# MotorBoardDev.net
KiCad netlist of a schematic drawn in EAGLE
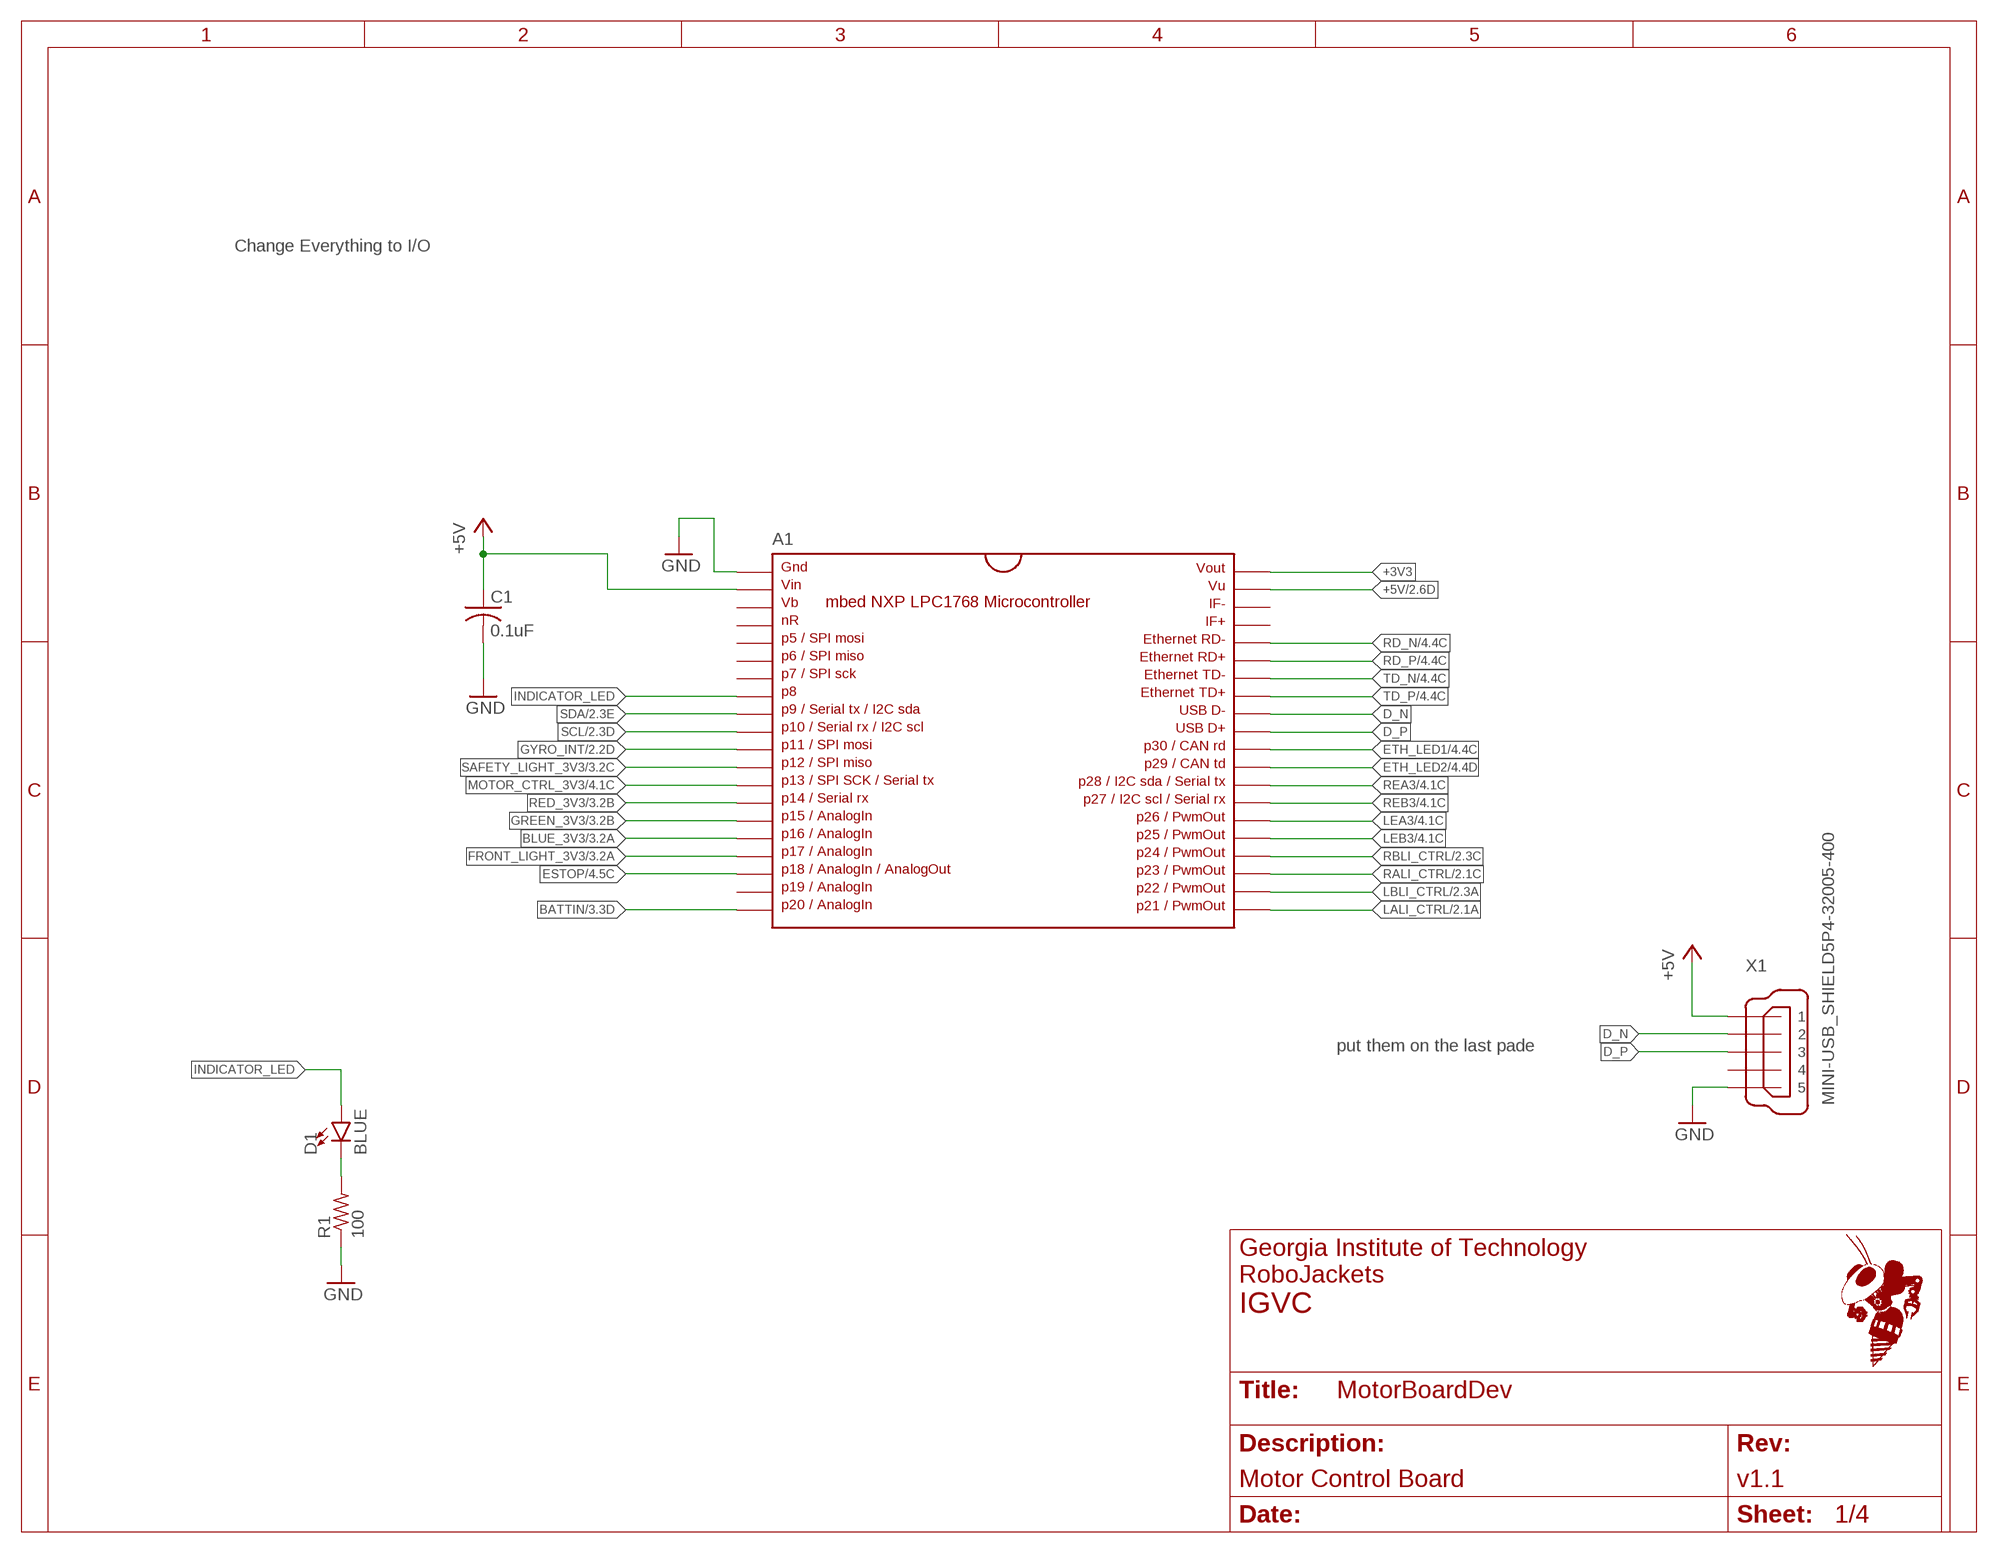
[diagram p0: schematic, sheet 1]
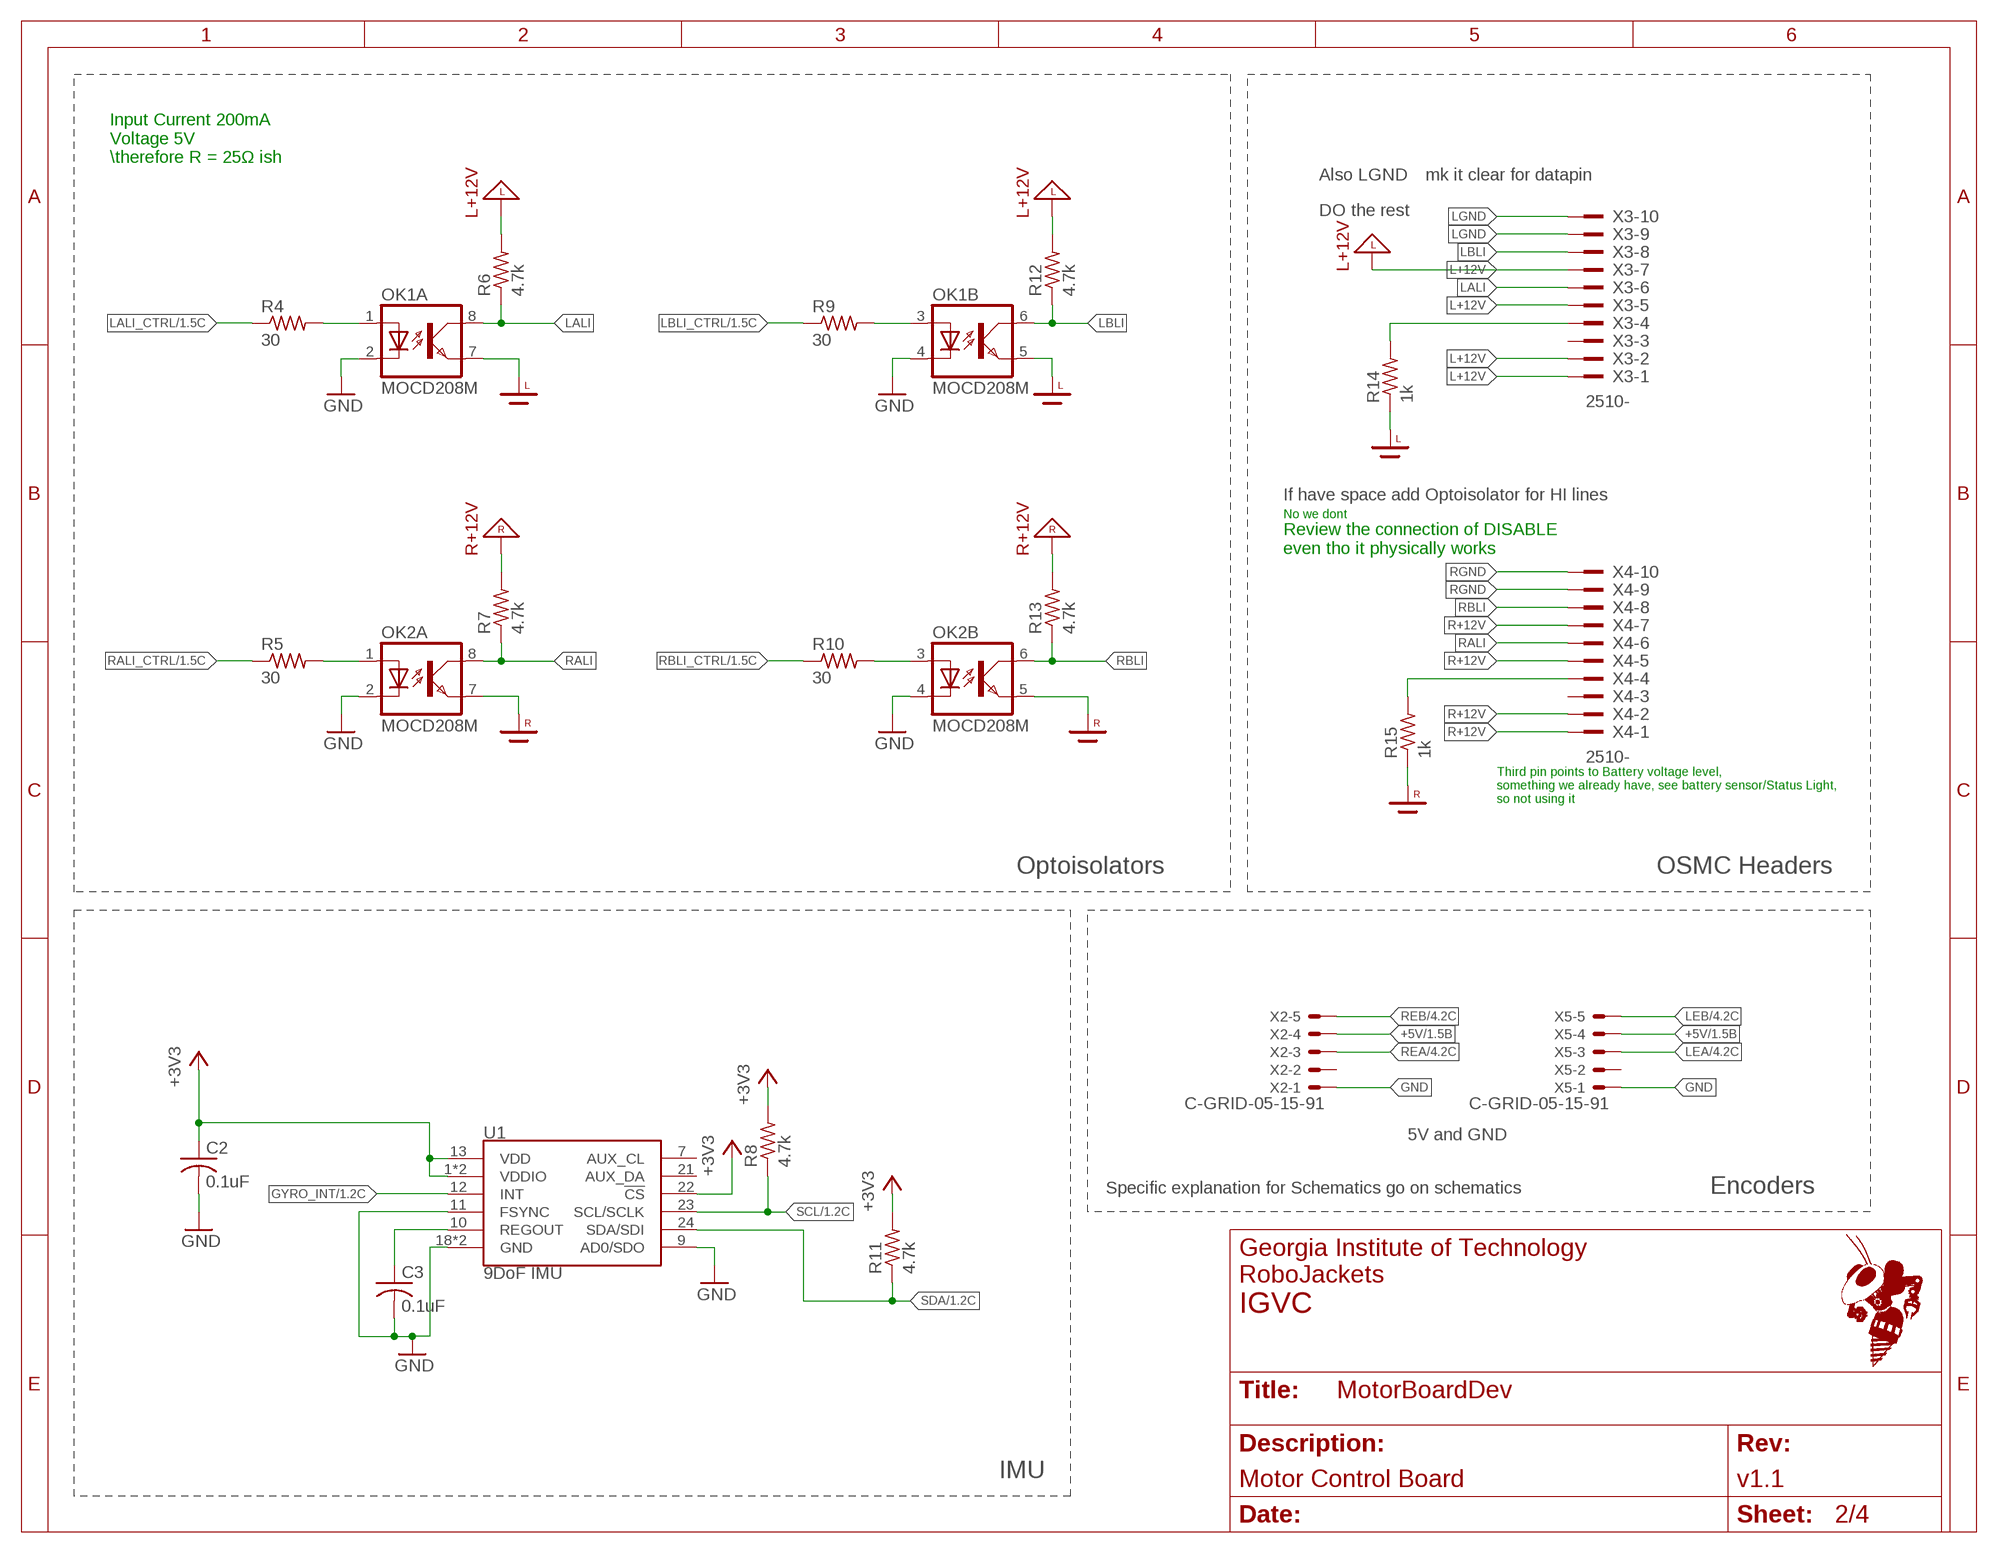
[diagram p1: schematic, sheet 2]
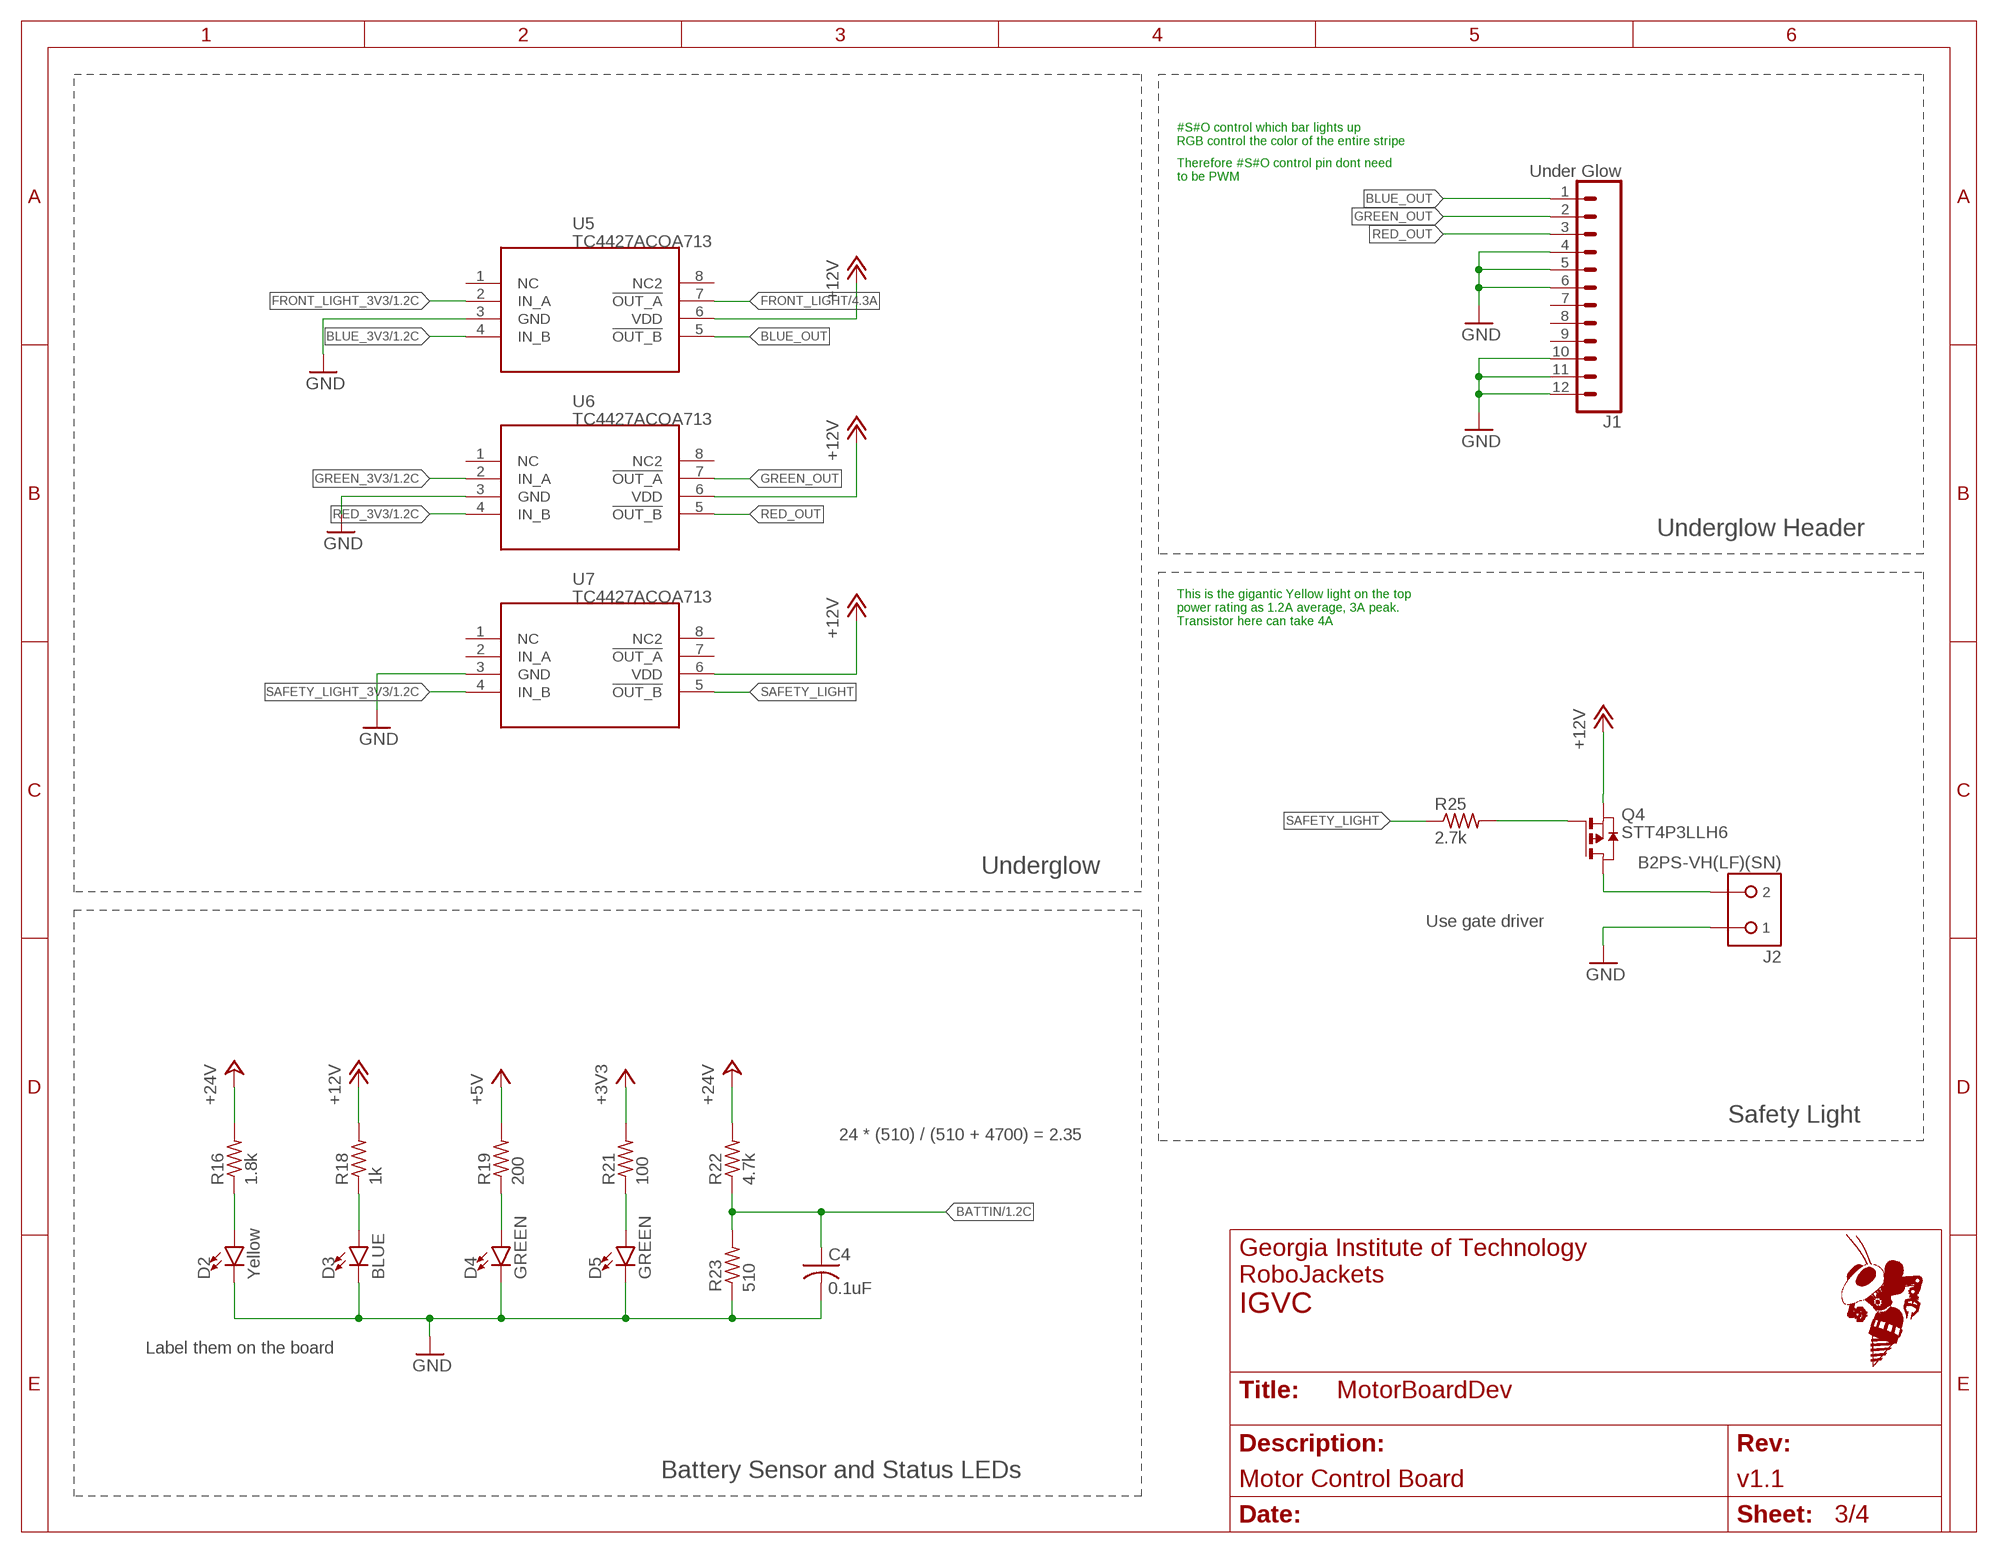
[diagram p2: schematic, sheet 3]
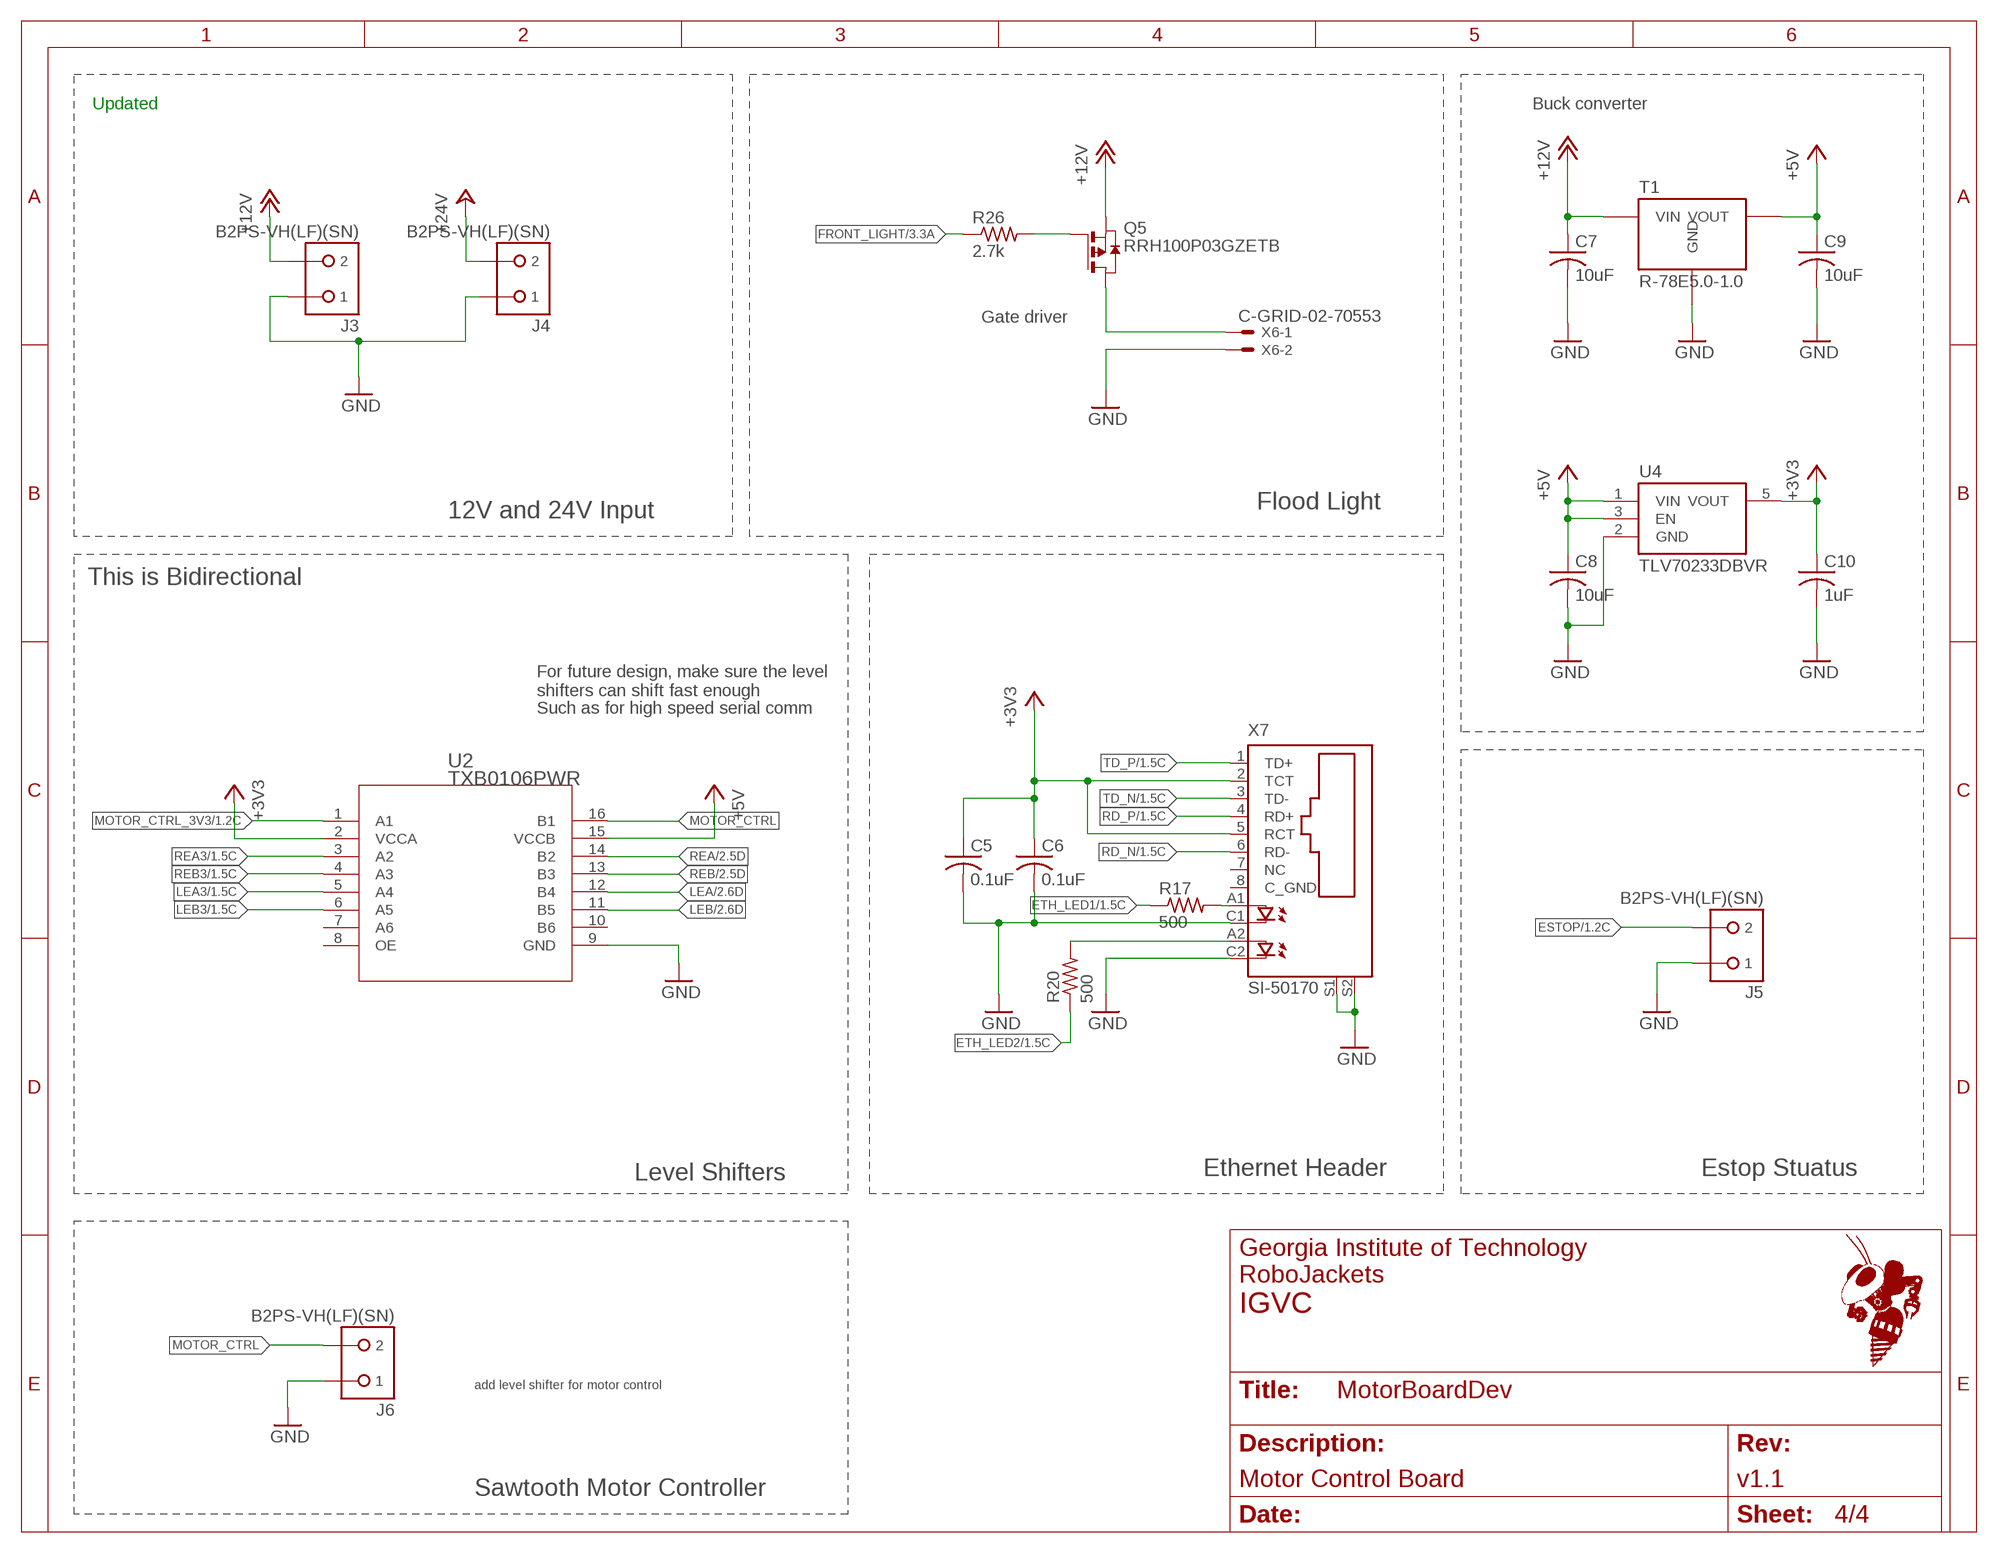
[diagram p3: schematic, sheet 4]

(export (version "E")
  (design (tool "Eeschema 10.0.6"))
  (components
    (comp (ref "A1")
      (value "MBED1768")
      (footprint "eagle-import:SPARKFUN-BOARDS_DIL40_0.9")
      (libsource (lib "eagle-import") (part "SPARKFUN-BOARDS_MBED_NXP_LPC1768"))
    )
    (comp (ref "C1")
      (value "0.1uF")
      (footprint "eagle-import:C0603")
      (libsource (lib "eagle-import") (part "C-USC0603"))
    )
    (comp (ref "D1")
      (value "BLUE")
      (footprint "eagle-import:LED-0603")
      (libsource (lib "eagle-import") (part "LED-BLUE0603"))
    )
    (comp (ref "R1")
      (value "100")
      (footprint "eagle-import:R0603")
      (libsource (lib "eagle-import") (part "R-US_R0603"))
    )
    (comp (ref "X1")
      (value "MINI-USB_SHIELD5P4-32005-400")
      (footprint "eagle-import:32005-400")
      (libsource (lib "eagle-import") (part "MINI-USB_SHIELD5P4-32005-400"))
    )
    (comp (ref "C4")
      (value "0.1uF")
      (footprint "eagle-import:C0603")
      (libsource (lib "eagle-import") (part "C-USC0603"))
    )
    (comp (ref "D2")
      (value "Yellow")
      (footprint "eagle-import:LED-0603")
      (libsource (lib "eagle-import") (part "LED-YELLOW0603"))
    )
    (comp (ref "D3")
      (value "BLUE")
      (footprint "eagle-import:LED-0603")
      (libsource (lib "eagle-import") (part "LED-BLUE0603"))
    )
    (comp (ref "D4")
      (value "GREEN")
      (footprint "eagle-import:LED-0603")
      (libsource (lib "eagle-import") (part "LED-GREEN0603"))
    )
    (comp (ref "D5")
      (value "GREEN")
      (footprint "eagle-import:LED-0603")
      (libsource (lib "eagle-import") (part "LED-GREEN0603"))
    )
    (comp (ref "J1")
      (value "Under Glow")
      (footprint "eagle-import:1X12_LOCK_LONGPADS")
      (libsource (lib "eagle-import") (part "CONN_12LOCK_LONGPADS"))
    )
    (comp (ref "J2")
      (value "B2PS-VH(LF)(SN)")
      (footprint "eagle-import:B2PS-CENTERED")
      (libsource (lib "eagle-import") (part "B2P?-VH(LF)(SN)S"))
    )
    (comp (ref "Q4")
      (value "STT4P3LLH6")
      (footprint "eagle-import:SOT23-6")
      (libsource (lib "eagle-import") (part "STT4P3LLH6"))
    )
    (comp (ref "R16")
      (value "1.8k")
      (footprint "eagle-import:R0603")
      (libsource (lib "eagle-import") (part "R-US_R0603"))
    )
    (comp (ref "R18")
      (value "1k")
      (footprint "eagle-import:R0603")
      (libsource (lib "eagle-import") (part "R-US_R0603"))
    )
    (comp (ref "R19")
      (value "200")
      (footprint "eagle-import:R0603")
      (libsource (lib "eagle-import") (part "R-US_R0603"))
    )
    (comp (ref "R21")
      (value "100")
      (footprint "eagle-import:R0603")
      (libsource (lib "eagle-import") (part "R-US_R0603"))
    )
    (comp (ref "R22")
      (value "4.7k")
      (footprint "eagle-import:R0603")
      (libsource (lib "eagle-import") (part "R-US_R0603"))
    )
    (comp (ref "R23")
      (value "510")
      (footprint "eagle-import:R0603")
      (libsource (lib "eagle-import") (part "R-US_R0603"))
    )
    (comp (ref "R25")
      (value "2.7k")
      (footprint "eagle-import:R0603")
      (libsource (lib "eagle-import") (part "R-US_R0603"))
    )
    (comp (ref "U5")
      (value "TC4427ACOA713")
      (footprint "eagle-import:SOIC-8")
      (libsource (lib "eagle-import") (part "TC4427ACOA713"))
    )
    (comp (ref "U6")
      (value "TC4427ACOA713")
      (footprint "eagle-import:SOIC-8")
      (libsource (lib "eagle-import") (part "TC4427ACOA713"))
    )
    (comp (ref "U7")
      (value "TC4427ACOA713")
      (footprint "eagle-import:SOIC-8")
      (libsource (lib "eagle-import") (part "TC4427ACOA713"))
    )
    (comp (ref "C5")
      (value "0.1uF")
      (footprint "eagle-import:C0603")
      (libsource (lib "eagle-import") (part "C-USC0603"))
    )
    (comp (ref "C6")
      (value "0.1uF")
      (footprint "eagle-import:C0603")
      (libsource (lib "eagle-import") (part "C-USC0603"))
    )
    (comp (ref "C7")
      (value "10uF")
      (footprint "eagle-import:C0805")
      (libsource (lib "eagle-import") (part "C-USC0805"))
    )
    (comp (ref "C8")
      (value "10uF")
      (footprint "eagle-import:C0805")
      (libsource (lib "eagle-import") (part "C-USC0805"))
    )
    (comp (ref "C9")
      (value "10uF")
      (footprint "eagle-import:C0805")
      (libsource (lib "eagle-import") (part "C-USC0805"))
    )
    (comp (ref "C10")
      (value "1uF")
      (footprint "eagle-import:C0805")
      (libsource (lib "eagle-import") (part "C-USC0805"))
    )
    (comp (ref "J3")
      (value "B2PS-VH(LF)(SN)")
      (footprint "eagle-import:B2PS-CENTERED")
      (libsource (lib "eagle-import") (part "B2P?-VH(LF)(SN)S"))
    )
    (comp (ref "J4")
      (value "B2PS-VH(LF)(SN)")
      (footprint "eagle-import:B2PS-CENTERED")
      (libsource (lib "eagle-import") (part "B2P?-VH(LF)(SN)S"))
    )
    (comp (ref "J5")
      (value "B2PS-VH(LF)(SN)")
      (footprint "eagle-import:B2PS-CENTERED")
      (libsource (lib "eagle-import") (part "B2P?-VH(LF)(SN)S"))
    )
    (comp (ref "J6")
      (value "B2PS-VH(LF)(SN)")
      (footprint "eagle-import:B2PS-CENTERED")
      (libsource (lib "eagle-import") (part "B2P?-VH(LF)(SN)S"))
    )
    (comp (ref "Q5")
      (value "RRH100P03GZETB")
      (footprint "eagle-import:SOIC-8")
      (libsource (lib "eagle-import") (part "RRH100P03GZETB"))
    )
    (comp (ref "R17")
      (value "500")
      (footprint "eagle-import:R0603")
      (libsource (lib "eagle-import") (part "R-US_R0603"))
    )
    (comp (ref "R20")
      (value "500")
      (footprint "eagle-import:R0603")
      (libsource (lib "eagle-import") (part "R-US_R0603"))
    )
    (comp (ref "R26")
      (value "2.7k")
      (footprint "eagle-import:R0603")
      (libsource (lib "eagle-import") (part "R-US_R0603"))
    )
    (comp (ref "T1")
      (value "R-78E5.0-1.0")
      (footprint "eagle-import:R-78E")
      (libsource (lib "eagle-import") (part "R-78E5.0-1.0"))
    )
    (comp (ref "U2")
      (value "TXB0106PWR")
      (footprint "eagle-import:PW16")
      (libsource (lib "eagle-import") (part "TXB0106PWR"))
    )
    (comp (ref "U4")
      (value "TLV70233DBVR")
      (footprint "eagle-import:SOT-23-5")
      (libsource (lib "eagle-import") (part "TLV70233DBVR"))
    )
    (comp (ref "X6")
      (value "C-GRID-02-70553")
      (footprint "eagle-import:70553-02")
      (libsource (lib "eagle-import") (part "C-GRID-02-70553"))
    )
    (comp (ref "X7")
      (value "SI-50170")
      (footprint "eagle-import:SI-50170")
      (libsource (lib "eagle-import") (part "SI-50170"))
    )
    (comp (ref "C2")
      (value "0.1uF")
      (footprint "eagle-import:C0603")
      (libsource (lib "eagle-import") (part "C-USC0603"))
    )
    (comp (ref "C3")
      (value "0.1uF")
      (footprint "eagle-import:C0603")
      (libsource (lib "eagle-import") (part "C-USC0603"))
    )
    (comp (ref "OK1")
      (value "MOCD208M")
      (footprint "eagle-import:SOIC08-FAIRCHILD")
      (fields (field (name "MF") "FAIRCHILD SEMICONDUCTOR"))
      (libsource (lib "eagle-import") (part "MOCD20M8"))
    )
    (comp (ref "OK2")
      (value "MOCD208M")
      (footprint "eagle-import:SOIC08-FAIRCHILD")
      (fields (field (name "MF") "FAIRCHILD SEMICONDUCTOR"))
      (libsource (lib "eagle-import") (part "MOCD20M8"))
    )
    (comp (ref "R4")
      (value "30")
      (footprint "eagle-import:R0603")
      (libsource (lib "eagle-import") (part "R-US_R0603"))
    )
    (comp (ref "R5")
      (value "30")
      (footprint "eagle-import:R0603")
      (libsource (lib "eagle-import") (part "R-US_R0603"))
    )
    (comp (ref "R6")
      (value "4.7k")
      (footprint "eagle-import:R0603")
      (libsource (lib "eagle-import") (part "R-US_R0603"))
    )
    (comp (ref "R7")
      (value "4.7k")
      (footprint "eagle-import:R0603")
      (libsource (lib "eagle-import") (part "R-US_R0603"))
    )
    (comp (ref "R8")
      (value "4.7k")
      (footprint "eagle-import:R0603")
      (libsource (lib "eagle-import") (part "R-US_R0603"))
    )
    (comp (ref "R9")
      (value "30")
      (footprint "eagle-import:R0603")
      (libsource (lib "eagle-import") (part "R-US_R0603"))
    )
    (comp (ref "R10")
      (value "30")
      (footprint "eagle-import:R0603")
      (libsource (lib "eagle-import") (part "R-US_R0603"))
    )
    (comp (ref "R11")
      (value "4.7k")
      (footprint "eagle-import:R0603")
      (libsource (lib "eagle-import") (part "R-US_R0603"))
    )
    (comp (ref "R12")
      (value "4.7k")
      (footprint "eagle-import:R0603")
      (libsource (lib "eagle-import") (part "R-US_R0603"))
    )
    (comp (ref "R13")
      (value "4.7k")
      (footprint "eagle-import:R0603")
      (libsource (lib "eagle-import") (part "R-US_R0603"))
    )
    (comp (ref "R14")
      (value "1k")
      (footprint "eagle-import:R0603")
      (libsource (lib "eagle-import") (part "R-US_R0603"))
    )
    (comp (ref "R15")
      (value "1k")
      (footprint "eagle-import:R0603")
      (libsource (lib "eagle-import") (part "R-US_R0603"))
    )
    (comp (ref "U1")
      (value "9DoF IMU")
      (footprint "eagle-import:QFN24-3X3")
      (libsource (lib "eagle-import") (part "MPU-9250"))
    )
    (comp (ref "X2")
      (value "C-GRID-05-15-91")
      (footprint "eagle-import:15-91-05")
      (libsource (lib "eagle-import") (part "C-GRID-05-15-91"))
    )
    (comp (ref "X3")
      (value "2510-")
      (footprint "eagle-import:PAK100_2500-10")
      (fields (field (name "MF") "3M") (field (name "MPN") "2510-6002UB"))
      (libsource (lib "eagle-import") (part "2510-"))
    )
    (comp (ref "X4")
      (value "2510-")
      (footprint "eagle-import:PAK100_2500-10")
      (fields (field (name "MF") "3M") (field (name "MPN") "2510-6002UB"))
      (libsource (lib "eagle-import") (part "2510-"))
    )
    (comp (ref "X5")
      (value "C-GRID-05-15-91")
      (footprint "eagle-import:15-91-05")
      (libsource (lib "eagle-import") (part "C-GRID-05-15-91"))
    )
  )
  (nets
    (net (code "1") (name "+3V3") (class "Default")
      (node (ref "A1") (pin "40") (pinfunction "P$40_40") (pintype "bidirectional"))
      (node (ref "C10") (pin "1") (pinfunction "1_1") (pintype "passive"))
      (node (ref "C2") (pin "1") (pinfunction "1_1") (pintype "passive"))
      (node (ref "C5") (pin "1") (pinfunction "1_1") (pintype "passive"))
      (node (ref "C6") (pin "1") (pinfunction "1_1") (pintype "passive"))
      (node (ref "R11") (pin "2") (pinfunction "2_2") (pintype "passive"))
      (node (ref "R21") (pin "2") (pinfunction "2_2") (pintype "passive"))
      (node (ref "R8") (pin "2") (pinfunction "2_2") (pintype "passive"))
      (node (ref "U1") (pin "1") (pinfunction "VDDIO_1") (pintype "bidirectional"))
      (node (ref "U1") (pin "13") (pinfunction "VDD_13") (pintype "bidirectional"))
      (node (ref "U1") (pin "22") (pinfunction "~{CS}_22") (pintype "bidirectional"))
      (node (ref "U1") (pin "8") (pinfunction "VDDIO_8") (pintype "bidirectional"))
      (node (ref "U2") (pin "2") (pinfunction "VCCA_2") (pintype "power_in"))
      (node (ref "U4") (pin "5") (pinfunction "VOUT_5") (pintype "bidirectional"))
      (node (ref "X7") (pin "2") (pinfunction "TCT_2") (pintype "passive"))
      (node (ref "X7") (pin "5") (pinfunction "RCT_5") (pintype "passive"))
    )
    (net (code "2") (name "+5V") (class "Default")
      (node (ref "A1") (pin "2") (pinfunction "P$2_2") (pintype "bidirectional"))
      (node (ref "A1") (pin "39") (pinfunction "P$39_39") (pintype "bidirectional"))
      (node (ref "C1") (pin "1") (pinfunction "1_1") (pintype "passive"))
      (node (ref "C8") (pin "1") (pinfunction "1_1") (pintype "passive"))
      (node (ref "C9") (pin "1") (pinfunction "1_1") (pintype "passive"))
      (node (ref "R19") (pin "2") (pinfunction "2_2") (pintype "passive"))
      (node (ref "T1") (pin "3") (pinfunction "VOUT_3") (pintype "bidirectional"))
      (node (ref "U2") (pin "15") (pinfunction "VCCB_15") (pintype "power_in"))
      (node (ref "U4") (pin "1") (pinfunction "VIN_1") (pintype "bidirectional"))
      (node (ref "U4") (pin "3") (pinfunction "EN_3") (pintype "bidirectional"))
      (node (ref "X1") (pin "1") (pinfunction "1_1") (pintype "passive"))
      (node (ref "X2") (pin "4") (pinfunction "S_4") (pintype "passive"))
      (node (ref "X5") (pin "4") (pinfunction "S_4") (pintype "passive"))
    )
    (net (code "3") (name "+12V") (class "Default")
      (node (ref "C7") (pin "1") (pinfunction "1_1") (pintype "passive"))
      (node (ref "J3") (pin "2") (pinfunction "2_2") (pintype "bidirectional"))
      (node (ref "Q4") (pin "4") (pinfunction "S_4") (pintype "passive"))
      (node (ref "Q5") (pin "1") (pinfunction "S_1") (pintype "passive"))
      (node (ref "Q5") (pin "2") (pinfunction "S_2") (pintype "passive"))
      (node (ref "Q5") (pin "3") (pinfunction "S_3") (pintype "passive"))
      (node (ref "R18") (pin "2") (pinfunction "2_2") (pintype "passive"))
      (node (ref "T1") (pin "1") (pinfunction "VIN_1") (pintype "bidirectional"))
      (node (ref "U5") (pin "6") (pinfunction "VDD_6") (pintype "bidirectional"))
      (node (ref "U6") (pin "6") (pinfunction "VDD_6") (pintype "bidirectional"))
      (node (ref "U7") (pin "6") (pinfunction "VDD_6") (pintype "bidirectional"))
    )
    (net (code "4") (name "+24V") (class "Default")
      (node (ref "J4") (pin "2") (pinfunction "2_2") (pintype "bidirectional"))
      (node (ref "R16") (pin "2") (pinfunction "2_2") (pintype "passive"))
      (node (ref "R22") (pin "2") (pinfunction "2_2") (pintype "passive"))
    )
    (net (code "5") (name "BATTIN") (class "Default")
      (node (ref "A1") (pin "20") (pinfunction "P$20_20") (pintype "bidirectional"))
      (node (ref "C4") (pin "1") (pinfunction "1_1") (pintype "passive"))
      (node (ref "R22") (pin "1") (pinfunction "1_1") (pintype "passive"))
      (node (ref "R23") (pin "2") (pinfunction "2_2") (pintype "passive"))
    )
    (net (code "6") (name "BLUE_3V3") (class "Default")
      (node (ref "A1") (pin "16") (pinfunction "P$16_16") (pintype "bidirectional"))
      (node (ref "U5") (pin "4") (pinfunction "IN_B_4") (pintype "bidirectional"))
    )
    (net (code "7") (name "BLUE_OUT") (class "Default")
      (node (ref "J1") (pin "1") (pinfunction "1_1") (pintype "passive"))
      (node (ref "U5") (pin "5") (pinfunction "~{OUT_B}_5") (pintype "bidirectional"))
    )
    (net (code "8") (name "D_N") (class "Default")
      (node (ref "A1") (pin "32") (pinfunction "P$32_32") (pintype "bidirectional"))
      (node (ref "X1") (pin "2") (pinfunction "2_2") (pintype "passive"))
    )
    (net (code "9") (name "D_P") (class "Default")
      (node (ref "A1") (pin "31") (pinfunction "P$31_31") (pintype "bidirectional"))
      (node (ref "X1") (pin "3") (pinfunction "3_3") (pintype "passive"))
    )
    (net (code "10") (name "ESTOP") (class "Default")
      (node (ref "A1") (pin "18") (pinfunction "P$18_18") (pintype "bidirectional"))
      (node (ref "J5") (pin "2") (pinfunction "2_2") (pintype "bidirectional"))
    )
    (net (code "11") (name "ETH_LED1") (class "Default")
      (node (ref "A1") (pin "30") (pinfunction "P$30_30") (pintype "bidirectional"))
      (node (ref "R17") (pin "1") (pinfunction "1_1") (pintype "passive"))
    )
    (net (code "12") (name "ETH_LED2") (class "Default")
      (node (ref "A1") (pin "29") (pinfunction "P$29_29") (pintype "bidirectional"))
      (node (ref "R20") (pin "1") (pinfunction "1_1") (pintype "passive"))
    )
    (net (code "13") (name "FRONT_LIGHT") (class "Default")
      (node (ref "R26") (pin "1") (pinfunction "1_1") (pintype "passive"))
      (node (ref "U5") (pin "7") (pinfunction "~{OUT_A}_7") (pintype "bidirectional"))
    )
    (net (code "14") (name "FRONT_LIGHT_3V3") (class "Default")
      (node (ref "A1") (pin "17") (pinfunction "P$17_17") (pintype "bidirectional"))
      (node (ref "U5") (pin "2") (pinfunction "IN_A_2") (pintype "bidirectional"))
    )
    (net (code "15") (name "GND") (class "Default")
      (node (ref "A1") (pin "1") (pinfunction "P$1_1") (pintype "bidirectional"))
      (node (ref "C1") (pin "2") (pinfunction "2_2") (pintype "passive"))
      (node (ref "C10") (pin "2") (pinfunction "2_2") (pintype "passive"))
      (node (ref "C2") (pin "2") (pinfunction "2_2") (pintype "passive"))
      (node (ref "C3") (pin "2") (pinfunction "2_2") (pintype "passive"))
      (node (ref "C4") (pin "2") (pinfunction "2_2") (pintype "passive"))
      (node (ref "C5") (pin "2") (pinfunction "2_2") (pintype "passive"))
      (node (ref "C6") (pin "2") (pinfunction "2_2") (pintype "passive"))
      (node (ref "C7") (pin "2") (pinfunction "2_2") (pintype "passive"))
      (node (ref "C8") (pin "2") (pinfunction "2_2") (pintype "passive"))
      (node (ref "C9") (pin "2") (pinfunction "2_2") (pintype "passive"))
      (node (ref "D2") (pin "C") (pinfunction "C_C") (pintype "passive"))
      (node (ref "D3") (pin "C") (pinfunction "C_C") (pintype "passive"))
      (node (ref "D4") (pin "C") (pinfunction "C_C") (pintype "passive"))
      (node (ref "D5") (pin "C") (pinfunction "C_C") (pintype "passive"))
      (node (ref "J1") (pin "10") (pinfunction "10_10") (pintype "passive"))
      (node (ref "J1") (pin "11") (pinfunction "11_11") (pintype "passive"))
      (node (ref "J1") (pin "12") (pinfunction "12_12") (pintype "passive"))
      (node (ref "J1") (pin "4") (pinfunction "4_4") (pintype "passive"))
      (node (ref "J1") (pin "5") (pinfunction "5_5") (pintype "passive"))
      (node (ref "J1") (pin "6") (pinfunction "6_6") (pintype "passive"))
      (node (ref "J2") (pin "1") (pinfunction "1_1") (pintype "bidirectional"))
      (node (ref "J3") (pin "1") (pinfunction "1_1") (pintype "bidirectional"))
      (node (ref "J4") (pin "1") (pinfunction "1_1") (pintype "bidirectional"))
      (node (ref "J5") (pin "1") (pinfunction "1_1") (pintype "bidirectional"))
      (node (ref "J6") (pin "1") (pinfunction "1_1") (pintype "bidirectional"))
      (node (ref "OK1") (pin "2") (pinfunction "C_2") (pintype "passive"))
      (node (ref "OK1") (pin "4") (pinfunction "C_4") (pintype "passive"))
      (node (ref "OK2") (pin "2") (pinfunction "C_2") (pintype "passive"))
      (node (ref "OK2") (pin "4") (pinfunction "C_4") (pintype "passive"))
      (node (ref "R1") (pin "1") (pinfunction "1_1") (pintype "passive"))
      (node (ref "R23") (pin "1") (pinfunction "1_1") (pintype "passive"))
      (node (ref "T1") (pin "2") (pinfunction "GND_2") (pintype "bidirectional"))
      (node (ref "U1") (pin "11") (pinfunction "FSYNC_11") (pintype "bidirectional"))
      (node (ref "U1") (pin "18") (pinfunction "GND_18") (pintype "bidirectional"))
      (node (ref "U1") (pin "20") (pinfunction "GND_20") (pintype "bidirectional"))
      (node (ref "U1") (pin "9") (pinfunction "AD0/SDO_9") (pintype "bidirectional"))
      (node (ref "U2") (pin "9") (pinfunction "GND_9") (pintype "power_in"))
      (node (ref "U4") (pin "2") (pinfunction "GND_2") (pintype "bidirectional"))
      (node (ref "U5") (pin "3") (pinfunction "GND_3") (pintype "bidirectional"))
      (node (ref "U6") (pin "3") (pinfunction "GND_3") (pintype "bidirectional"))
      (node (ref "U7") (pin "3") (pinfunction "GND_3") (pintype "bidirectional"))
      (node (ref "X1") (pin "5") (pinfunction "5_5") (pintype "passive"))
      (node (ref "X2") (pin "1") (pinfunction "S_1") (pintype "passive"))
      (node (ref "X5") (pin "1") (pinfunction "S_1") (pintype "passive"))
      (node (ref "X6") (pin "2") (pinfunction "S_2") (pintype "passive"))
      (node (ref "X7") (pin "C1") (pinfunction "C_C1") (pintype "passive"))
      (node (ref "X7") (pin "C2") (pinfunction "C1_C2") (pintype "passive"))
      (node (ref "X7") (pin "S1") (pinfunction "S1_S1") (pintype "passive"))
      (node (ref "X7") (pin "S2") (pinfunction "S2_S2") (pintype "passive"))
    )
    (net (code "16") (name "GREEN_3V3") (class "Default")
      (node (ref "A1") (pin "15") (pinfunction "P$15_15") (pintype "bidirectional"))
      (node (ref "U6") (pin "2") (pinfunction "IN_A_2") (pintype "bidirectional"))
    )
    (net (code "17") (name "GREEN_OUT") (class "Default")
      (node (ref "J1") (pin "2") (pinfunction "2_2") (pintype "passive"))
      (node (ref "U6") (pin "7") (pinfunction "~{OUT_A}_7") (pintype "bidirectional"))
    )
    (net (code "18") (name "GYRO_INT") (class "Default")
      (node (ref "A1") (pin "11") (pinfunction "P$11_11") (pintype "bidirectional"))
      (node (ref "U1") (pin "12") (pinfunction "INT_12") (pintype "bidirectional"))
    )
    (net (code "19") (name "INDICATOR_LED") (class "Default")
      (node (ref "A1") (pin "8") (pinfunction "P$8_8") (pintype "bidirectional"))
      (node (ref "D1") (pin "A") (pinfunction "A_A") (pintype "passive"))
    )
    (net (code "20") (name "L+12V") (class "Default")
      (node (ref "R12") (pin "2") (pinfunction "2_2") (pintype "passive"))
      (node (ref "R6") (pin "2") (pinfunction "2_2") (pintype "passive"))
      (node (ref "X3") (pin "1") (pinfunction "KL_1") (pintype "passive"))
      (node (ref "X3") (pin "2") (pinfunction "KL_2") (pintype "passive"))
      (node (ref "X3") (pin "5") (pinfunction "KL_5") (pintype "passive"))
      (node (ref "X3") (pin "7") (pinfunction "KL_7") (pintype "passive"))
    )
    (net (code "21") (name "LALI") (class "Default")
      (node (ref "OK1") (pin "8") (pinfunction "COL_8") (pintype "passive"))
      (node (ref "R6") (pin "1") (pinfunction "1_1") (pintype "passive"))
      (node (ref "X3") (pin "6") (pinfunction "KL_6") (pintype "passive"))
    )
    (net (code "22") (name "LALI_CTRL") (class "Default")
      (node (ref "A1") (pin "21") (pinfunction "P$21_21") (pintype "bidirectional"))
      (node (ref "R4") (pin "1") (pinfunction "1_1") (pintype "passive"))
    )
    (net (code "23") (name "LBLI") (class "Default")
      (node (ref "OK1") (pin "6") (pinfunction "COL_6") (pintype "passive"))
      (node (ref "R12") (pin "1") (pinfunction "1_1") (pintype "passive"))
      (node (ref "X3") (pin "8") (pinfunction "KL_8") (pintype "passive"))
    )
    (net (code "24") (name "LBLI_CTRL") (class "Default")
      (node (ref "A1") (pin "22") (pinfunction "P$22_22") (pintype "bidirectional"))
      (node (ref "R9") (pin "1") (pinfunction "1_1") (pintype "passive"))
    )
    (net (code "25") (name "LEA") (class "Default")
      (node (ref "U2") (pin "12") (pinfunction "B4_12") (pintype "bidirectional"))
      (node (ref "X5") (pin "3") (pinfunction "S_3") (pintype "passive"))
    )
    (net (code "26") (name "LEA3") (class "Default")
      (node (ref "A1") (pin "26") (pinfunction "P$26_26") (pintype "bidirectional"))
      (node (ref "U2") (pin "5") (pinfunction "A4_5") (pintype "bidirectional"))
    )
    (net (code "27") (name "LEB") (class "Default")
      (node (ref "U2") (pin "11") (pinfunction "B5_11") (pintype "bidirectional"))
      (node (ref "X5") (pin "5") (pinfunction "S_5") (pintype "passive"))
    )
    (net (code "28") (name "LEB3") (class "Default")
      (node (ref "A1") (pin "25") (pinfunction "P$25_25") (pintype "bidirectional"))
      (node (ref "U2") (pin "6") (pinfunction "A5_6") (pintype "bidirectional"))
    )
    (net (code "29") (name "LGND") (class "Default")
      (node (ref "OK1") (pin "5") (pinfunction "EMIT_5") (pintype "passive"))
      (node (ref "OK1") (pin "7") (pinfunction "EMIT_7") (pintype "passive"))
      (node (ref "R14") (pin "1") (pinfunction "1_1") (pintype "passive"))
      (node (ref "X3") (pin "10") (pinfunction "KL_10") (pintype "passive"))
      (node (ref "X3") (pin "9") (pinfunction "KL_9") (pintype "passive"))
    )
    (net (code "30") (name "MOTOR_CTRL") (class "Default")
      (node (ref "J6") (pin "2") (pinfunction "2_2") (pintype "bidirectional"))
      (node (ref "U2") (pin "16") (pinfunction "B1_16") (pintype "bidirectional"))
    )
    (net (code "31") (name "MOTOR_CTRL_3V3") (class "Default")
      (node (ref "A1") (pin "13") (pinfunction "P$13_13") (pintype "bidirectional"))
      (node (ref "U2") (pin "1") (pinfunction "A1_1") (pintype "bidirectional"))
    )
    (net (code "32") (name "Net-(D1-PadC)") (class "Default")
      (node (ref "D1") (pin "C") (pinfunction "C_C") (pintype "passive"))
      (node (ref "R1") (pin "2") (pinfunction "2_2") (pintype "passive"))
    )
    (net (code "33") (name "Net-(D2-PadA)") (class "Default")
      (node (ref "D2") (pin "A") (pinfunction "A_A") (pintype "passive"))
      (node (ref "R16") (pin "1") (pinfunction "1_1") (pintype "passive"))
    )
    (net (code "34") (name "Net-(D3-PadA)") (class "Default")
      (node (ref "D3") (pin "A") (pinfunction "A_A") (pintype "passive"))
      (node (ref "R18") (pin "1") (pinfunction "1_1") (pintype "passive"))
    )
    (net (code "35") (name "Net-(D4-PadA)") (class "Default")
      (node (ref "D4") (pin "A") (pinfunction "A_A") (pintype "passive"))
      (node (ref "R19") (pin "1") (pinfunction "1_1") (pintype "passive"))
    )
    (net (code "36") (name "Net-(D5-PadA)") (class "Default")
      (node (ref "D5") (pin "A") (pinfunction "A_A") (pintype "passive"))
      (node (ref "R21") (pin "1") (pinfunction "1_1") (pintype "passive"))
    )
    (net (code "37") (name "Net-(J2-Pad2)") (class "Default")
      (node (ref "J2") (pin "2") (pinfunction "2_2") (pintype "bidirectional"))
      (node (ref "Q4") (pin "1") (pinfunction "D_1") (pintype "passive"))
      (node (ref "Q4") (pin "2") (pinfunction "D_2") (pintype "passive"))
      (node (ref "Q4") (pin "5") (pinfunction "D_5") (pintype "passive"))
      (node (ref "Q4") (pin "6") (pinfunction "D_6") (pintype "passive"))
    )
    (net (code "38") (name "Net-(OK1A-A)") (class "Default")
      (node (ref "OK1") (pin "1") (pinfunction "A_1") (pintype "passive"))
      (node (ref "R4") (pin "2") (pinfunction "2_2") (pintype "passive"))
    )
    (net (code "39") (name "Net-(OK1B-A)") (class "Default")
      (node (ref "OK1") (pin "3") (pinfunction "A_3") (pintype "passive"))
      (node (ref "R9") (pin "2") (pinfunction "2_2") (pintype "passive"))
    )
    (net (code "40") (name "Net-(OK2A-A)") (class "Default")
      (node (ref "OK2") (pin "1") (pinfunction "A_1") (pintype "passive"))
      (node (ref "R5") (pin "2") (pinfunction "2_2") (pintype "passive"))
    )
    (net (code "41") (name "Net-(OK2B-A)") (class "Default")
      (node (ref "OK2") (pin "3") (pinfunction "A_3") (pintype "passive"))
      (node (ref "R10") (pin "2") (pinfunction "2_2") (pintype "passive"))
    )
    (net (code "42") (name "Net-(Q4-G)") (class "Default")
      (node (ref "Q4") (pin "3") (pinfunction "G_3") (pintype "passive"))
      (node (ref "R25") (pin "2") (pinfunction "2_2") (pintype "passive"))
    )
    (net (code "43") (name "Net-(Q5-G)") (class "Default")
      (node (ref "Q5") (pin "4") (pinfunction "G_4") (pintype "passive"))
      (node (ref "R26") (pin "2") (pinfunction "2_2") (pintype "passive"))
    )
    (net (code "44") (name "Net-(U1-REGOUT)") (class "Default")
      (node (ref "C3") (pin "1") (pinfunction "1_1") (pintype "passive"))
      (node (ref "U1") (pin "10") (pinfunction "REGOUT_10") (pintype "bidirectional"))
    )
    (net (code "45") (name "Net-(X3E-KL)") (class "Default")
      (node (ref "R14") (pin "2") (pinfunction "2_2") (pintype "passive"))
      (node (ref "X3") (pin "4") (pinfunction "KL_4") (pintype "passive"))
    )
    (net (code "46") (name "Net-(X4E-KL)") (class "Default")
      (node (ref "R15") (pin "2") (pinfunction "2_2") (pintype "passive"))
      (node (ref "X4") (pin "4") (pinfunction "KL_4") (pintype "passive"))
    )
    (net (code "47") (name "Net-(X6A-S)") (class "Default")
      (node (ref "Q5") (pin "5") (pinfunction "D_5") (pintype "passive"))
      (node (ref "Q5") (pin "6") (pinfunction "D_6") (pintype "passive"))
      (node (ref "Q5") (pin "7") (pinfunction "D_7") (pintype "passive"))
      (node (ref "Q5") (pin "8") (pinfunction "D_8") (pintype "passive"))
      (node (ref "X6") (pin "1") (pinfunction "S_1") (pintype "passive"))
    )
    (net (code "48") (name "Net-(X7-A)") (class "Default")
      (node (ref "R17") (pin "2") (pinfunction "2_2") (pintype "passive"))
      (node (ref "X7") (pin "A1") (pinfunction "A_A1") (pintype "passive"))
    )
    (net (code "49") (name "Net-(X7-A1)") (class "Default")
      (node (ref "R20") (pin "2") (pinfunction "2_2") (pintype "passive"))
      (node (ref "X7") (pin "A2") (pinfunction "A1_A2") (pintype "passive"))
    )
    (net (code "50") (name "R+12V") (class "Default")
      (node (ref "R13") (pin "2") (pinfunction "2_2") (pintype "passive"))
      (node (ref "R7") (pin "2") (pinfunction "2_2") (pintype "passive"))
      (node (ref "X4") (pin "1") (pinfunction "KL_1") (pintype "passive"))
      (node (ref "X4") (pin "2") (pinfunction "KL_2") (pintype "passive"))
      (node (ref "X4") (pin "5") (pinfunction "KL_5") (pintype "passive"))
      (node (ref "X4") (pin "7") (pinfunction "KL_7") (pintype "passive"))
    )
    (net (code "51") (name "RALI") (class "Default")
      (node (ref "OK2") (pin "8") (pinfunction "COL_8") (pintype "passive"))
      (node (ref "R7") (pin "1") (pinfunction "1_1") (pintype "passive"))
      (node (ref "X4") (pin "6") (pinfunction "KL_6") (pintype "passive"))
    )
    (net (code "52") (name "RALI_CTRL") (class "Default")
      (node (ref "A1") (pin "23") (pinfunction "P$23_23") (pintype "bidirectional"))
      (node (ref "R5") (pin "1") (pinfunction "1_1") (pintype "passive"))
    )
    (net (code "53") (name "RBLI") (class "Default")
      (node (ref "OK2") (pin "6") (pinfunction "COL_6") (pintype "passive"))
      (node (ref "R13") (pin "1") (pinfunction "1_1") (pintype "passive"))
      (node (ref "X4") (pin "8") (pinfunction "KL_8") (pintype "passive"))
    )
    (net (code "54") (name "RBLI_CTRL") (class "Default")
      (node (ref "A1") (pin "24") (pinfunction "P$24_24") (pintype "bidirectional"))
      (node (ref "R10") (pin "1") (pinfunction "1_1") (pintype "passive"))
    )
    (net (code "55") (name "RD_N") (class "Default")
      (node (ref "A1") (pin "36") (pinfunction "P$36_36") (pintype "bidirectional"))
      (node (ref "X7") (pin "6") (pinfunction "RD-_6") (pintype "passive"))
    )
    (net (code "56") (name "RD_P") (class "Default")
      (node (ref "A1") (pin "35") (pinfunction "P$35_35") (pintype "bidirectional"))
      (node (ref "X7") (pin "4") (pinfunction "RD+_4") (pintype "passive"))
    )
    (net (code "57") (name "REA") (class "Default")
      (node (ref "U2") (pin "14") (pinfunction "B2_14") (pintype "bidirectional"))
      (node (ref "X2") (pin "3") (pinfunction "S_3") (pintype "passive"))
    )
    (net (code "58") (name "REA3") (class "Default")
      (node (ref "A1") (pin "28") (pinfunction "P$28_28") (pintype "bidirectional"))
      (node (ref "U2") (pin "3") (pinfunction "A2_3") (pintype "bidirectional"))
    )
    (net (code "59") (name "REB") (class "Default")
      (node (ref "U2") (pin "13") (pinfunction "B3_13") (pintype "bidirectional"))
      (node (ref "X2") (pin "5") (pinfunction "S_5") (pintype "passive"))
    )
    (net (code "60") (name "REB3") (class "Default")
      (node (ref "A1") (pin "27") (pinfunction "P$27_27") (pintype "bidirectional"))
      (node (ref "U2") (pin "4") (pinfunction "A3_4") (pintype "bidirectional"))
    )
    (net (code "61") (name "RED_3V3") (class "Default")
      (node (ref "A1") (pin "14") (pinfunction "P$14_14") (pintype "bidirectional"))
      (node (ref "U6") (pin "4") (pinfunction "IN_B_4") (pintype "bidirectional"))
    )
    (net (code "62") (name "RED_OUT") (class "Default")
      (node (ref "J1") (pin "3") (pinfunction "3_3") (pintype "passive"))
      (node (ref "U6") (pin "5") (pinfunction "~{OUT_B}_5") (pintype "bidirectional"))
    )
    (net (code "63") (name "RGND") (class "Default")
      (node (ref "OK2") (pin "5") (pinfunction "EMIT_5") (pintype "passive"))
      (node (ref "OK2") (pin "7") (pinfunction "EMIT_7") (pintype "passive"))
      (node (ref "R15") (pin "1") (pinfunction "1_1") (pintype "passive"))
      (node (ref "X4") (pin "10") (pinfunction "KL_10") (pintype "passive"))
      (node (ref "X4") (pin "9") (pinfunction "KL_9") (pintype "passive"))
    )
    (net (code "64") (name "SAFETY_LIGHT") (class "Default")
      (node (ref "R25") (pin "1") (pinfunction "1_1") (pintype "passive"))
      (node (ref "U7") (pin "5") (pinfunction "~{OUT_B}_5") (pintype "bidirectional"))
    )
    (net (code "65") (name "SAFETY_LIGHT_3V3") (class "Default")
      (node (ref "A1") (pin "12") (pinfunction "P$12_12") (pintype "bidirectional"))
      (node (ref "U7") (pin "4") (pinfunction "IN_B_4") (pintype "bidirectional"))
    )
    (net (code "66") (name "SCL") (class "Default")
      (node (ref "A1") (pin "10") (pinfunction "P$10_10") (pintype "bidirectional"))
      (node (ref "R8") (pin "1") (pinfunction "1_1") (pintype "passive"))
      (node (ref "U1") (pin "23") (pinfunction "SCL/SCLK_23") (pintype "bidirectional"))
    )
    (net (code "67") (name "SDA") (class "Default")
      (node (ref "A1") (pin "9") (pinfunction "P$9_9") (pintype "bidirectional"))
      (node (ref "R11") (pin "1") (pinfunction "1_1") (pintype "passive"))
      (node (ref "U1") (pin "24") (pinfunction "SDA/SDI_24") (pintype "bidirectional"))
    )
    (net (code "68") (name "TD_N") (class "Default")
      (node (ref "A1") (pin "34") (pinfunction "P$34_34") (pintype "bidirectional"))
      (node (ref "X7") (pin "3") (pinfunction "TD-_3") (pintype "passive"))
    )
    (net (code "69") (name "TD_P") (class "Default")
      (node (ref "A1") (pin "33") (pinfunction "P$33_33") (pintype "bidirectional"))
      (node (ref "X7") (pin "1") (pinfunction "TD+_1") (pintype "passive"))
    )
    (net (code "70") (name "unconnected-(A1-P$3-Pad3)") (class "Default")
      (node (ref "A1") (pin "3") (pinfunction "P$3_3") (pintype "bidirectional"))
    )
    (net (code "71") (name "unconnected-(A1-P$4-Pad4)") (class "Default")
      (node (ref "A1") (pin "4") (pinfunction "P$4_4") (pintype "bidirectional"))
    )
    (net (code "72") (name "unconnected-(A1-P$5-Pad5)") (class "Default")
      (node (ref "A1") (pin "5") (pinfunction "P$5_5") (pintype "bidirectional"))
    )
    (net (code "73") (name "unconnected-(A1-P$6-Pad6)") (class "Default")
      (node (ref "A1") (pin "6") (pinfunction "P$6_6") (pintype "bidirectional"))
    )
    (net (code "74") (name "unconnected-(A1-P$7-Pad7)") (class "Default")
      (node (ref "A1") (pin "7") (pinfunction "P$7_7") (pintype "bidirectional"))
    )
    (net (code "75") (name "unconnected-(A1-P$19-Pad19)") (class "Default")
      (node (ref "A1") (pin "19") (pinfunction "P$19_19") (pintype "bidirectional"))
    )
    (net (code "76") (name "unconnected-(A1-P$37-Pad37)") (class "Default")
      (node (ref "A1") (pin "37") (pinfunction "P$37_37") (pintype "bidirectional"))
    )
    (net (code "77") (name "unconnected-(A1-P$38-Pad38)") (class "Default")
      (node (ref "A1") (pin "38") (pinfunction "P$38_38") (pintype "bidirectional"))
    )
    (net (code "78") (name "unconnected-(J1-Pad7)") (class "Default")
      (node (ref "J1") (pin "7") (pinfunction "7_7") (pintype "passive"))
    )
    (net (code "79") (name "unconnected-(J1-Pad8)") (class "Default")
      (node (ref "J1") (pin "8") (pinfunction "8_8") (pintype "passive"))
    )
    (net (code "80") (name "unconnected-(J1-Pad9)") (class "Default")
      (node (ref "J1") (pin "9") (pinfunction "9_9") (pintype "passive"))
    )
    (net (code "81") (name "unconnected-(U1-AUX_CL-Pad7)") (class "Default")
      (node (ref "U1") (pin "7") (pinfunction "AUX_CL_7") (pintype "bidirectional"))
    )
    (net (code "82") (name "unconnected-(U1-AUX_DA-Pad21)") (class "Default")
      (node (ref "U1") (pin "21") (pinfunction "AUX_DA_21") (pintype "bidirectional"))
    )
    (net (code "83") (name "unconnected-(U2-A6-Pad7)") (class "Default")
      (node (ref "U2") (pin "7") (pinfunction "A6_7") (pintype "bidirectional"))
    )
    (net (code "84") (name "unconnected-(U2-B6-Pad10)") (class "Default")
      (node (ref "U2") (pin "10") (pinfunction "B6_10") (pintype "bidirectional"))
    )
    (net (code "85") (name "unconnected-(U2-OE-Pad8)") (class "Default")
      (node (ref "U2") (pin "8") (pinfunction "OE_8") (pintype "output"))
    )
    (net (code "86") (name "unconnected-(U5-NC-Pad1)") (class "Default")
      (node (ref "U5") (pin "1") (pinfunction "NC_1") (pintype "bidirectional"))
    )
    (net (code "87") (name "unconnected-(U5-NC2-Pad8)") (class "Default")
      (node (ref "U5") (pin "8") (pinfunction "NC2_8") (pintype "bidirectional"))
    )
    (net (code "88") (name "unconnected-(U6-NC-Pad1)") (class "Default")
      (node (ref "U6") (pin "1") (pinfunction "NC_1") (pintype "bidirectional"))
    )
    (net (code "89") (name "unconnected-(U6-NC2-Pad8)") (class "Default")
      (node (ref "U6") (pin "8") (pinfunction "NC2_8") (pintype "bidirectional"))
    )
    (net (code "90") (name "unconnected-(U7-IN_A-Pad2)") (class "Default")
      (node (ref "U7") (pin "2") (pinfunction "IN_A_2") (pintype "bidirectional"))
    )
    (net (code "91") (name "unconnected-(U7-NC-Pad1)") (class "Default")
      (node (ref "U7") (pin "1") (pinfunction "NC_1") (pintype "bidirectional"))
    )
    (net (code "92") (name "unconnected-(U7-NC2-Pad8)") (class "Default")
      (node (ref "U7") (pin "8") (pinfunction "NC2_8") (pintype "bidirectional"))
    )
    (net (code "93") (name "unconnected-(U7-~{OUT_A}-Pad7)") (class "Default")
      (node (ref "U7") (pin "7") (pinfunction "~{OUT_A}_7") (pintype "bidirectional"))
    )
    (net (code "94") (name "unconnected-(X1-Pad4)") (class "Default")
      (node (ref "X1") (pin "4") (pinfunction "4_4") (pintype "passive"))
    )
    (net (code "95") (name "unconnected-(X2B-S-Pad2)") (class "Default")
      (node (ref "X2") (pin "2") (pinfunction "S_2") (pintype "passive"))
    )
    (net (code "96") (name "unconnected-(X3D-KL-Pad3)") (class "Default")
      (node (ref "X3") (pin "3") (pinfunction "KL_3") (pintype "passive"))
    )
    (net (code "97") (name "unconnected-(X4D-KL-Pad3)") (class "Default")
      (node (ref "X4") (pin "3") (pinfunction "KL_3") (pintype "passive"))
    )
    (net (code "98") (name "unconnected-(X5B-S-Pad2)") (class "Default")
      (node (ref "X5") (pin "2") (pinfunction "S_2") (pintype "passive"))
    )
    (net (code "99") (name "unconnected-(X7-C_GND-Pad8)") (class "Default")
      (node (ref "X7") (pin "8") (pinfunction "C_GND_8") (pintype "passive"))
    )
    (net (code "100") (name "unconnected-(X7-NC-Pad7)") (class "Default")
      (node (ref "X7") (pin "7") (pinfunction "NC_7") (pintype "passive"))
    )
  )
)
